# Dosing_CTRLR_HMI.net
KiCad netlist of a schematic drawn in EAGLE
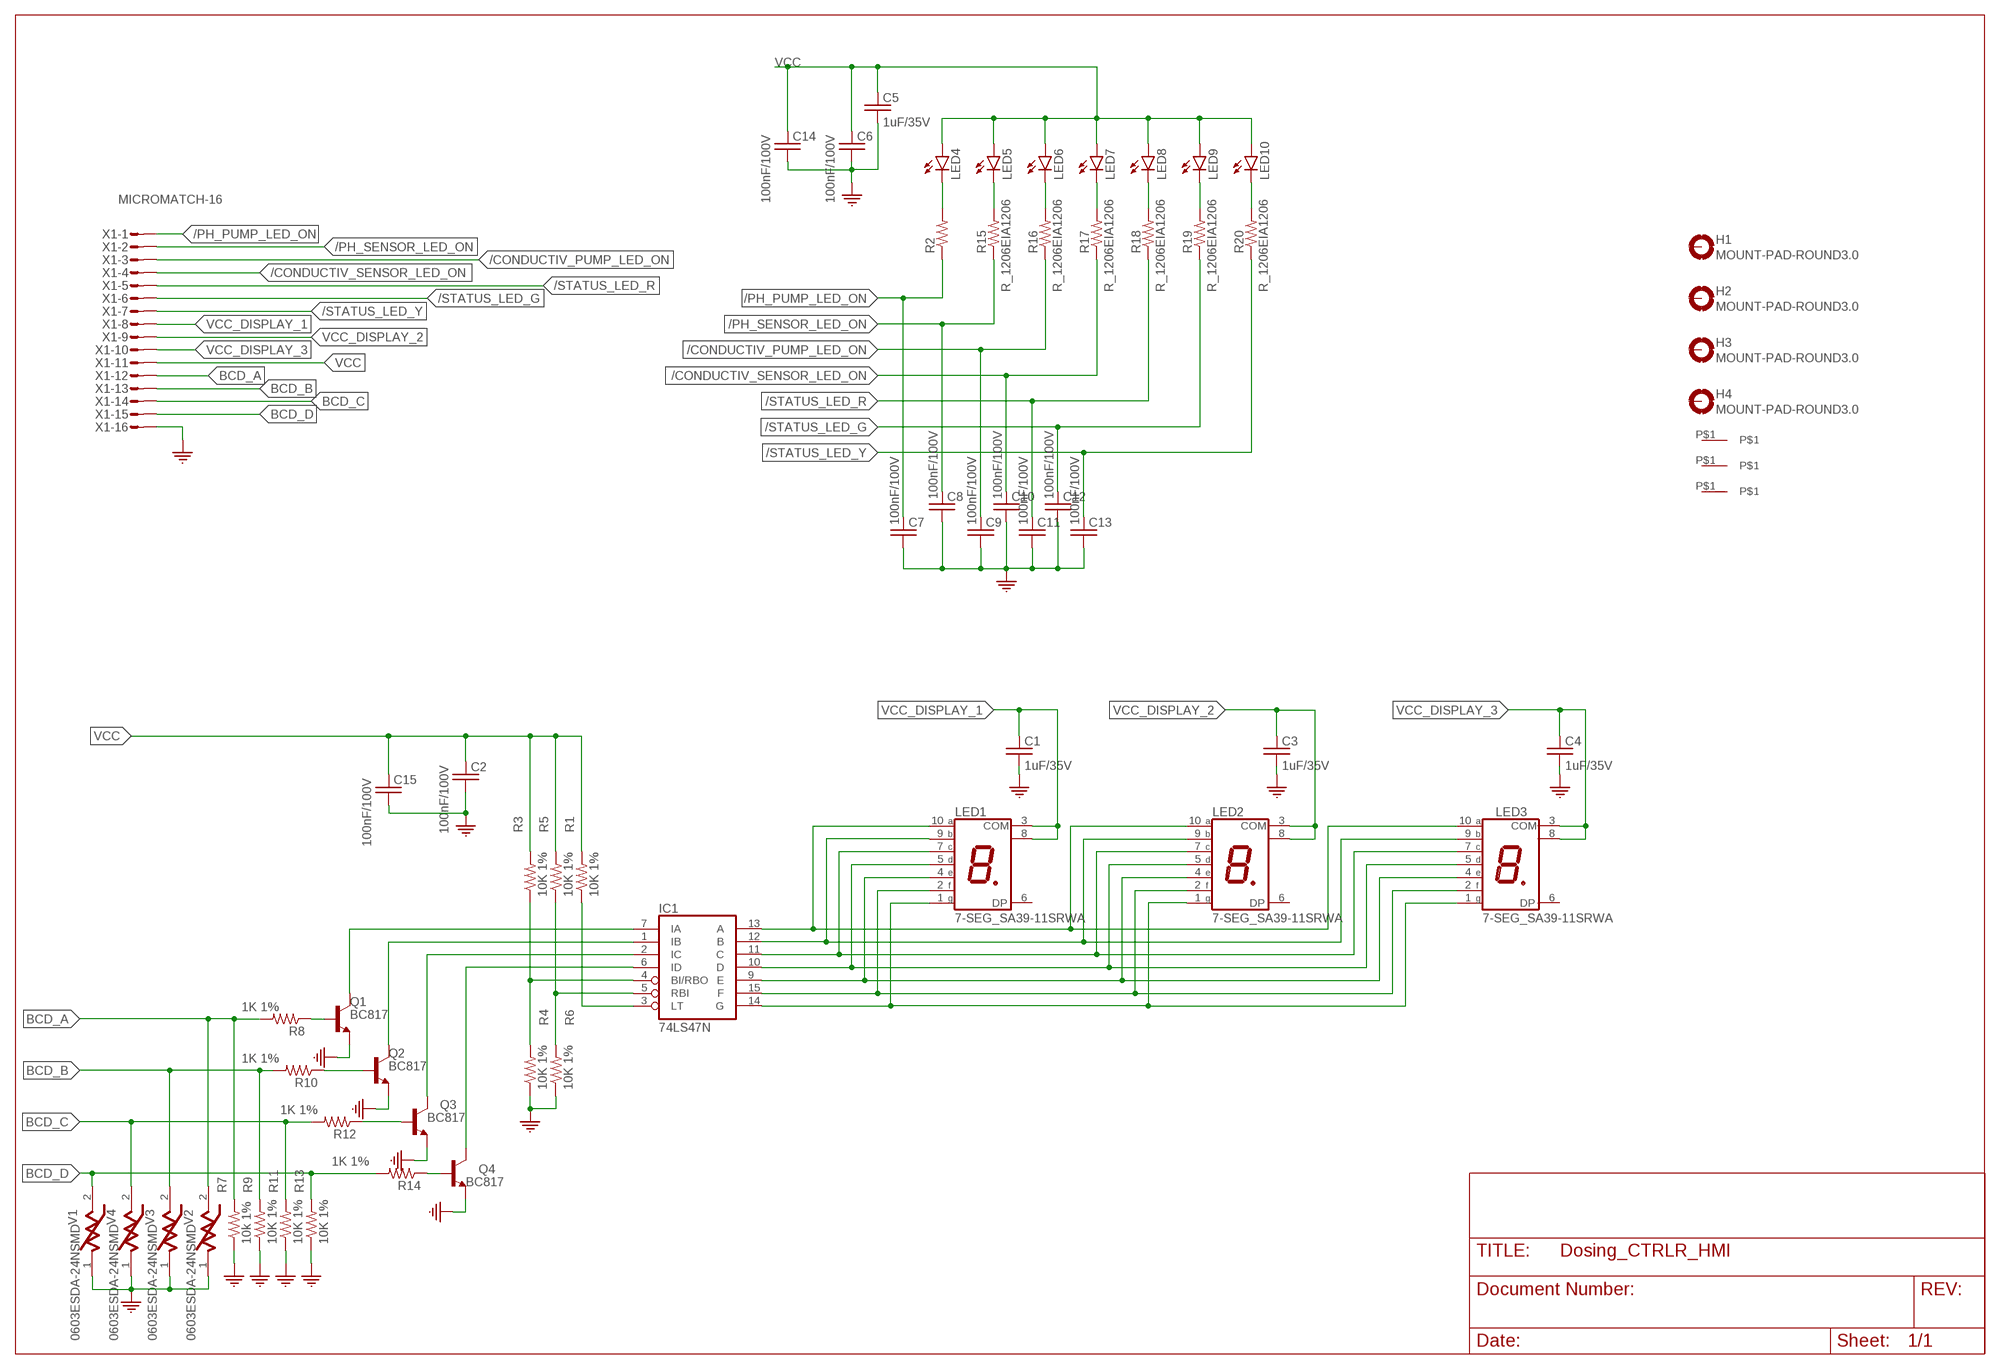
[diagram p0: schematic, sheet 1]

(export (version "E")
  (design (tool "Eeschema 10.0.6"))
  (components
    (comp (ref "C1")
      (value "1uF/35V")
      (footprint "eagle-import:EIA0603")
      (libsource (lib "eagle-import") (part "C_0603EIA0603"))
    )
    (comp (ref "C2")
      (value "100nF/100V")
      (footprint "eagle-import:EIA0603")
      (libsource (lib "eagle-import") (part "C_0603EIA0603"))
    )
    (comp (ref "C3")
      (value "1uF/35V")
      (footprint "eagle-import:EIA0603")
      (libsource (lib "eagle-import") (part "C_0603EIA0603"))
    )
    (comp (ref "C4")
      (value "1uF/35V")
      (footprint "eagle-import:EIA0603")
      (libsource (lib "eagle-import") (part "C_0603EIA0603"))
    )
    (comp (ref "C5")
      (value "1uF/35V")
      (footprint "eagle-import:EIA0603")
      (libsource (lib "eagle-import") (part "C_0603EIA0603"))
    )
    (comp (ref "C6")
      (value "100nF/100V")
      (footprint "eagle-import:EIA0603")
      (libsource (lib "eagle-import") (part "C_0603EIA0603"))
    )
    (comp (ref "C7")
      (value "100nF/100V")
      (footprint "eagle-import:EIA0603")
      (libsource (lib "eagle-import") (part "C_0603EIA0603"))
    )
    (comp (ref "C8")
      (value "100nF/100V")
      (footprint "eagle-import:EIA0603")
      (libsource (lib "eagle-import") (part "C_0603EIA0603"))
    )
    (comp (ref "C9")
      (value "100nF/100V")
      (footprint "eagle-import:EIA0603")
      (libsource (lib "eagle-import") (part "C_0603EIA0603"))
    )
    (comp (ref "C10")
      (value "100nF/100V")
      (footprint "eagle-import:EIA0603")
      (libsource (lib "eagle-import") (part "C_0603EIA0603"))
    )
    (comp (ref "C11")
      (value "100nF/100V")
      (footprint "eagle-import:EIA0603")
      (libsource (lib "eagle-import") (part "C_0603EIA0603"))
    )
    (comp (ref "C12")
      (value "100nF/100V")
      (footprint "eagle-import:EIA0603")
      (libsource (lib "eagle-import") (part "C_0603EIA0603"))
    )
    (comp (ref "C13")
      (value "100nF/100V")
      (footprint "eagle-import:EIA0603")
      (libsource (lib "eagle-import") (part "C_0603EIA0603"))
    )
    (comp (ref "C14")
      (value "100nF/100V")
      (footprint "eagle-import:EIA0603")
      (libsource (lib "eagle-import") (part "C_0603EIA0603"))
    )
    (comp (ref "C15")
      (value "100nF/100V")
      (footprint "eagle-import:EIA0603")
      (libsource (lib "eagle-import") (part "C_0603EIA0603"))
    )
    (comp (ref "FID1")
      (value "FIDUCIAL")
      (footprint "eagle-import:FIDUCIAL")
      (libsource (lib "eagle-import") (part "FIDUCIAL"))
    )
    (comp (ref "FID2")
      (value "FIDUCIAL")
      (footprint "eagle-import:FIDUCIAL")
      (libsource (lib "eagle-import") (part "FIDUCIAL"))
    )
    (comp (ref "FID3")
      (value "FIDUCIAL")
      (footprint "eagle-import:FIDUCIAL")
      (libsource (lib "eagle-import") (part "FIDUCIAL"))
    )
    (comp (ref "H1")
      (value "MOUNT-PAD-ROUND3.0")
      (footprint "eagle-import:3,0-PAD")
      (libsource (lib "eagle-import") (part "MOUNT-PAD-ROUND3.0"))
    )
    (comp (ref "H2")
      (value "MOUNT-PAD-ROUND3.0")
      (footprint "eagle-import:3,0-PAD")
      (libsource (lib "eagle-import") (part "MOUNT-PAD-ROUND3.0"))
    )
    (comp (ref "H3")
      (value "MOUNT-PAD-ROUND3.0")
      (footprint "eagle-import:3,0-PAD")
      (libsource (lib "eagle-import") (part "MOUNT-PAD-ROUND3.0"))
    )
    (comp (ref "H4")
      (value "MOUNT-PAD-ROUND3.0")
      (footprint "eagle-import:3,0-PAD")
      (libsource (lib "eagle-import") (part "MOUNT-PAD-ROUND3.0"))
    )
    (comp (ref "IC1")
      (value "74LS47N")
      (footprint "eagle-import:DIL16")
      (libsource (lib "eagle-import") (part "7447NLS"))
    )
    (comp (ref "LED1")
      (value "7-SEG_SA39-11SRWA")
      (footprint "eagle-import:SA39-11SRWA")
      (libsource (lib "eagle-import") (part "7-SEG_SA39-11SRWA"))
    )
    (comp (ref "LED2")
      (value "7-SEG_SA39-11SRWA")
      (footprint "eagle-import:SA39-11SRWA")
      (libsource (lib "eagle-import") (part "7-SEG_SA39-11SRWA"))
    )
    (comp (ref "LED3")
      (value "7-SEG_SA39-11SRWA")
      (footprint "eagle-import:SA39-11SRWA")
      (libsource (lib "eagle-import") (part "7-SEG_SA39-11SRWA"))
    )
    (comp (ref "LED4")
      (value "LED5MM")
      (footprint "eagle-import:LED5MM")
      (libsource (lib "eagle-import") (part "LED5MM"))
    )
    (comp (ref "LED5")
      (value "LED5MM")
      (footprint "eagle-import:LED5MM")
      (libsource (lib "eagle-import") (part "LED5MM"))
    )
    (comp (ref "LED6")
      (value "LED5MM")
      (footprint "eagle-import:LED5MM")
      (libsource (lib "eagle-import") (part "LED5MM"))
    )
    (comp (ref "LED7")
      (value "LED5MM")
      (footprint "eagle-import:LED5MM")
      (libsource (lib "eagle-import") (part "LED5MM"))
    )
    (comp (ref "LED8")
      (value "LED5MM")
      (footprint "eagle-import:LED5MM")
      (libsource (lib "eagle-import") (part "LED5MM"))
    )
    (comp (ref "LED9")
      (value "LED5MM")
      (footprint "eagle-import:LED5MM")
      (libsource (lib "eagle-import") (part "LED5MM"))
    )
    (comp (ref "LED10")
      (value "LED5MM")
      (footprint "eagle-import:LED5MM")
      (libsource (lib "eagle-import") (part "LED5MM"))
    )
    (comp (ref "Q1")
      (value "BC817")
      (footprint "eagle-import:SOT23")
      (fields (field (name "MFR") "NXP"))
      (libsource (lib "eagle-import") (part "BC817"))
    )
    (comp (ref "Q2")
      (value "BC817")
      (footprint "eagle-import:SOT23")
      (fields (field (name "MFR") "NXP"))
      (libsource (lib "eagle-import") (part "BC817"))
    )
    (comp (ref "Q3")
      (value "BC817")
      (footprint "eagle-import:SOT23")
      (fields (field (name "MFR") "NXP"))
      (libsource (lib "eagle-import") (part "BC817"))
    )
    (comp (ref "Q4")
      (value "BC817")
      (footprint "eagle-import:SOT23")
      (fields (field (name "MFR") "NXP"))
      (libsource (lib "eagle-import") (part "BC817"))
    )
    (comp (ref "R1")
      (value "10K 1%")
      (footprint "eagle-import:EIA0603")
      (libsource (lib "eagle-import") (part "R_0603"))
    )
    (comp (ref "R2")
      (value "R_1206EIA1206")
      (footprint "eagle-import:EIA1206")
      (libsource (lib "eagle-import") (part "R_1206EIA1206"))
    )
    (comp (ref "R3")
      (value "10K 1%")
      (footprint "eagle-import:EIA0603")
      (libsource (lib "eagle-import") (part "R_0603"))
    )
    (comp (ref "R4")
      (value "10K 1%")
      (footprint "eagle-import:EIA0603")
      (libsource (lib "eagle-import") (part "R_0603"))
    )
    (comp (ref "R5")
      (value "10K 1%")
      (footprint "eagle-import:EIA0603")
      (libsource (lib "eagle-import") (part "R_0603"))
    )
    (comp (ref "R6")
      (value "10K 1%")
      (footprint "eagle-import:EIA0603")
      (libsource (lib "eagle-import") (part "R_0603"))
    )
    (comp (ref "R7")
      (value "10k 1%")
      (footprint "eagle-import:EIA0603")
      (libsource (lib "eagle-import") (part "R_0603"))
    )
    (comp (ref "R8")
      (value "1K 1%")
      (footprint "eagle-import:EIA0603")
      (libsource (lib "eagle-import") (part "R_0603"))
    )
    (comp (ref "R9")
      (value "10K 1%")
      (footprint "eagle-import:EIA0603")
      (libsource (lib "eagle-import") (part "R_0603"))
    )
    (comp (ref "R10")
      (value "1K 1%")
      (footprint "eagle-import:EIA0603")
      (libsource (lib "eagle-import") (part "R_0603"))
    )
    (comp (ref "R11")
      (value "10K 1%")
      (footprint "eagle-import:EIA0603")
      (libsource (lib "eagle-import") (part "R_0603"))
    )
    (comp (ref "R12")
      (value "1K 1%")
      (footprint "eagle-import:EIA0603")
      (libsource (lib "eagle-import") (part "R_0603"))
    )
    (comp (ref "R13")
      (value "10K 1%")
      (footprint "eagle-import:EIA0603")
      (libsource (lib "eagle-import") (part "R_0603"))
    )
    (comp (ref "R14")
      (value "1K 1%")
      (footprint "eagle-import:EIA0603")
      (libsource (lib "eagle-import") (part "R_0603"))
    )
    (comp (ref "R15")
      (value "R_1206EIA1206")
      (footprint "eagle-import:EIA1206")
      (libsource (lib "eagle-import") (part "R_1206EIA1206"))
    )
    (comp (ref "R16")
      (value "R_1206EIA1206")
      (footprint "eagle-import:EIA1206")
      (libsource (lib "eagle-import") (part "R_1206EIA1206"))
    )
    (comp (ref "R17")
      (value "R_1206EIA1206")
      (footprint "eagle-import:EIA1206")
      (libsource (lib "eagle-import") (part "R_1206EIA1206"))
    )
    (comp (ref "R18")
      (value "R_1206EIA1206")
      (footprint "eagle-import:EIA1206")
      (libsource (lib "eagle-import") (part "R_1206EIA1206"))
    )
    (comp (ref "R19")
      (value "R_1206EIA1206")
      (footprint "eagle-import:EIA1206")
      (libsource (lib "eagle-import") (part "R_1206EIA1206"))
    )
    (comp (ref "R20")
      (value "R_1206EIA1206")
      (footprint "eagle-import:EIA1206")
      (libsource (lib "eagle-import") (part "R_1206EIA1206"))
    )
    (comp (ref "V1")
      (value "0603ESDA-24NSMD")
      (footprint "eagle-import:EIA0603")
      (fields (field (name "MFR") "Bourns"))
      (libsource (lib "eagle-import") (part "0603ESDA-24NSMD"))
    )
    (comp (ref "V2")
      (value "0603ESDA-24NSMD")
      (footprint "eagle-import:EIA0603")
      (fields (field (name "MFR") "Bourns"))
      (libsource (lib "eagle-import") (part "0603ESDA-24NSMD"))
    )
    (comp (ref "V3")
      (value "0603ESDA-24NSMD")
      (footprint "eagle-import:EIA0603")
      (fields (field (name "MFR") "Bourns"))
      (libsource (lib "eagle-import") (part "0603ESDA-24NSMD"))
    )
    (comp (ref "V4")
      (value "0603ESDA-24NSMD")
      (footprint "eagle-import:EIA0603")
      (fields (field (name "MFR") "Bourns"))
      (libsource (lib "eagle-import") (part "0603ESDA-24NSMD"))
    )
    (comp (ref "X1")
      (value "MICROMATCH-16")
      (footprint "eagle-import:MICROMATCH-16")
      (fields (field (name "MF") "FARNELL") (field (name "MPN") "8-215464-6"))
      (libsource (lib "eagle-import") (part "MICROMATCH-16"))
    )
  )
  (nets
    (net (code "1") (name "BCD_A") (class "Default")
      (node (ref "R7") (pin "2") (pinfunction "2_2") (pintype "passive"))
      (node (ref "R8") (pin "2") (pinfunction "2_2") (pintype "passive"))
      (node (ref "V2") (pin "2") (pinfunction "2_2") (pintype "passive"))
      (node (ref "X1") (pin "12") (pinfunction "S_12") (pintype "passive"))
    )
    (net (code "2") (name "BCD_B") (class "Default")
      (node (ref "R10") (pin "2") (pinfunction "2_2") (pintype "passive"))
      (node (ref "R9") (pin "2") (pinfunction "2_2") (pintype "passive"))
      (node (ref "V3") (pin "2") (pinfunction "2_2") (pintype "passive"))
      (node (ref "X1") (pin "13") (pinfunction "S_13") (pintype "passive"))
    )
    (net (code "3") (name "BCD_C") (class "Default")
      (node (ref "R11") (pin "2") (pinfunction "2_2") (pintype "passive"))
      (node (ref "R12") (pin "2") (pinfunction "2_2") (pintype "passive"))
      (node (ref "V4") (pin "2") (pinfunction "2_2") (pintype "passive"))
      (node (ref "X1") (pin "14") (pinfunction "S_14") (pintype "passive"))
    )
    (net (code "4") (name "BCD_D") (class "Default")
      (node (ref "R13") (pin "2") (pinfunction "2_2") (pintype "passive"))
      (node (ref "R14") (pin "2") (pinfunction "2_2") (pintype "passive"))
      (node (ref "V1") (pin "2") (pinfunction "2_2") (pintype "passive"))
      (node (ref "X1") (pin "15") (pinfunction "S_15") (pintype "passive"))
    )
    (net (code "5") (name "GND") (class "Default")
      (node (ref "C1") (pin "2") (pinfunction "2_2") (pintype "passive"))
      (node (ref "C10") (pin "2") (pinfunction "2_2") (pintype "passive"))
      (node (ref "C11") (pin "2") (pinfunction "2_2") (pintype "passive"))
      (node (ref "C12") (pin "2") (pinfunction "2_2") (pintype "passive"))
      (node (ref "C13") (pin "2") (pinfunction "2_2") (pintype "passive"))
      (node (ref "C14") (pin "2") (pinfunction "2_2") (pintype "passive"))
      (node (ref "C15") (pin "2") (pinfunction "2_2") (pintype "passive"))
      (node (ref "C2") (pin "2") (pinfunction "2_2") (pintype "passive"))
      (node (ref "C3") (pin "2") (pinfunction "2_2") (pintype "passive"))
      (node (ref "C4") (pin "2") (pinfunction "2_2") (pintype "passive"))
      (node (ref "C5") (pin "2") (pinfunction "2_2") (pintype "passive"))
      (node (ref "C6") (pin "2") (pinfunction "2_2") (pintype "passive"))
      (node (ref "C7") (pin "2") (pinfunction "2_2") (pintype "passive"))
      (node (ref "C8") (pin "2") (pinfunction "2_2") (pintype "passive"))
      (node (ref "C9") (pin "2") (pinfunction "2_2") (pintype "passive"))
      (node (ref "Q1") (pin "2") (pinfunction "E_2") (pintype "passive"))
      (node (ref "Q2") (pin "2") (pinfunction "E_2") (pintype "passive"))
      (node (ref "Q3") (pin "2") (pinfunction "E_2") (pintype "passive"))
      (node (ref "Q4") (pin "2") (pinfunction "E_2") (pintype "passive"))
      (node (ref "R11") (pin "1") (pinfunction "1_1") (pintype "passive"))
      (node (ref "R13") (pin "1") (pinfunction "1_1") (pintype "passive"))
      (node (ref "R4") (pin "1") (pinfunction "1_1") (pintype "passive"))
      (node (ref "R6") (pin "1") (pinfunction "1_1") (pintype "passive"))
      (node (ref "R7") (pin "1") (pinfunction "1_1") (pintype "passive"))
      (node (ref "R9") (pin "1") (pinfunction "1_1") (pintype "passive"))
      (node (ref "V1") (pin "1") (pinfunction "1_1") (pintype "passive"))
      (node (ref "V2") (pin "1") (pinfunction "1_1") (pintype "passive"))
      (node (ref "V3") (pin "1") (pinfunction "1_1") (pintype "passive"))
      (node (ref "V4") (pin "1") (pinfunction "1_1") (pintype "passive"))
      (node (ref "X1") (pin "16") (pinfunction "S_16") (pintype "passive"))
    )
    (net (code "6") (name "Net-(IC1A-A)") (class "Default")
      (node (ref "IC1") (pin "13") (pinfunction "A_13") (pintype "output"))
      (node (ref "LED1") (pin "10") (pinfunction "A_10") (pintype "passive"))
      (node (ref "LED2") (pin "10") (pinfunction "A_10") (pintype "passive"))
      (node (ref "LED3") (pin "10") (pinfunction "A_10") (pintype "passive"))
    )
    (net (code "7") (name "Net-(IC1A-B)") (class "Default")
      (node (ref "IC1") (pin "12") (pinfunction "B_12") (pintype "output"))
      (node (ref "LED1") (pin "9") (pinfunction "B_9") (pintype "passive"))
      (node (ref "LED2") (pin "9") (pinfunction "B_9") (pintype "passive"))
      (node (ref "LED3") (pin "9") (pinfunction "B_9") (pintype "passive"))
    )
    (net (code "8") (name "Net-(IC1A-BI{slash}RBO)") (class "Default")
      (node (ref "IC1") (pin "4") (pinfunction "BI/RBO_4") (pintype "input"))
      (node (ref "R3") (pin "1") (pinfunction "1_1") (pintype "passive"))
      (node (ref "R4") (pin "2") (pinfunction "2_2") (pintype "passive"))
    )
    (net (code "9") (name "Net-(IC1A-C)") (class "Default")
      (node (ref "IC1") (pin "11") (pinfunction "C_11") (pintype "output"))
      (node (ref "LED1") (pin "7") (pinfunction "C_7") (pintype "passive"))
      (node (ref "LED2") (pin "7") (pinfunction "C_7") (pintype "passive"))
      (node (ref "LED3") (pin "7") (pinfunction "C_7") (pintype "passive"))
    )
    (net (code "10") (name "Net-(IC1A-D)") (class "Default")
      (node (ref "IC1") (pin "10") (pinfunction "D_10") (pintype "output"))
      (node (ref "LED1") (pin "5") (pinfunction "D_5") (pintype "passive"))
      (node (ref "LED2") (pin "5") (pinfunction "D_5") (pintype "passive"))
      (node (ref "LED3") (pin "5") (pinfunction "D_5") (pintype "passive"))
    )
    (net (code "11") (name "Net-(IC1A-E)") (class "Default")
      (node (ref "IC1") (pin "9") (pinfunction "E_9") (pintype "output"))
      (node (ref "LED1") (pin "4") (pinfunction "E_4") (pintype "passive"))
      (node (ref "LED2") (pin "4") (pinfunction "E_4") (pintype "passive"))
      (node (ref "LED3") (pin "4") (pinfunction "E_4") (pintype "passive"))
    )
    (net (code "12") (name "Net-(IC1A-F)") (class "Default")
      (node (ref "IC1") (pin "15") (pinfunction "F_15") (pintype "output"))
      (node (ref "LED1") (pin "2") (pinfunction "F_2") (pintype "passive"))
      (node (ref "LED2") (pin "2") (pinfunction "F_2") (pintype "passive"))
      (node (ref "LED3") (pin "2") (pinfunction "F_2") (pintype "passive"))
    )
    (net (code "13") (name "Net-(IC1A-G)") (class "Default")
      (node (ref "IC1") (pin "14") (pinfunction "G_14") (pintype "output"))
      (node (ref "LED1") (pin "1") (pinfunction "G_1") (pintype "passive"))
      (node (ref "LED2") (pin "1") (pinfunction "G_1") (pintype "passive"))
      (node (ref "LED3") (pin "1") (pinfunction "G_1") (pintype "passive"))
    )
    (net (code "14") (name "Net-(IC1A-IA)") (class "Default")
      (node (ref "IC1") (pin "7") (pinfunction "IA_7") (pintype "input"))
      (node (ref "Q1") (pin "3") (pinfunction "C_3") (pintype "passive"))
    )
    (net (code "15") (name "Net-(IC1A-IB)") (class "Default")
      (node (ref "IC1") (pin "1") (pinfunction "IB_1") (pintype "input"))
      (node (ref "Q2") (pin "3") (pinfunction "C_3") (pintype "passive"))
    )
    (net (code "16") (name "Net-(IC1A-IC)") (class "Default")
      (node (ref "IC1") (pin "2") (pinfunction "IC_2") (pintype "input"))
      (node (ref "Q3") (pin "3") (pinfunction "C_3") (pintype "passive"))
    )
    (net (code "17") (name "Net-(IC1A-ID)") (class "Default")
      (node (ref "IC1") (pin "6") (pinfunction "ID_6") (pintype "input"))
      (node (ref "Q4") (pin "3") (pinfunction "C_3") (pintype "passive"))
    )
    (net (code "18") (name "Net-(IC1A-LT)") (class "Default")
      (node (ref "IC1") (pin "3") (pinfunction "LT_3") (pintype "input"))
      (node (ref "R1") (pin "1") (pinfunction "1_1") (pintype "passive"))
    )
    (net (code "19") (name "Net-(IC1A-RBI)") (class "Default")
      (node (ref "IC1") (pin "5") (pinfunction "RBI_5") (pintype "input"))
      (node (ref "R5") (pin "1") (pinfunction "1_1") (pintype "passive"))
      (node (ref "R6") (pin "2") (pinfunction "2_2") (pintype "passive"))
    )
    (net (code "20") (name "Net-(LED4-C)") (class "Default")
      (node (ref "LED4") (pin "K") (pinfunction "C_K") (pintype "passive"))
      (node (ref "R2") (pin "2") (pinfunction "2_2") (pintype "passive"))
    )
    (net (code "21") (name "Net-(LED5-C)") (class "Default")
      (node (ref "LED5") (pin "K") (pinfunction "C_K") (pintype "passive"))
      (node (ref "R15") (pin "2") (pinfunction "2_2") (pintype "passive"))
    )
    (net (code "22") (name "Net-(LED6-C)") (class "Default")
      (node (ref "LED6") (pin "K") (pinfunction "C_K") (pintype "passive"))
      (node (ref "R16") (pin "2") (pinfunction "2_2") (pintype "passive"))
    )
    (net (code "23") (name "Net-(LED7-C)") (class "Default")
      (node (ref "LED7") (pin "K") (pinfunction "C_K") (pintype "passive"))
      (node (ref "R17") (pin "2") (pinfunction "2_2") (pintype "passive"))
    )
    (net (code "24") (name "Net-(LED8-C)") (class "Default")
      (node (ref "LED8") (pin "K") (pinfunction "C_K") (pintype "passive"))
      (node (ref "R18") (pin "2") (pinfunction "2_2") (pintype "passive"))
    )
    (net (code "25") (name "Net-(LED9-C)") (class "Default")
      (node (ref "LED9") (pin "K") (pinfunction "C_K") (pintype "passive"))
      (node (ref "R19") (pin "2") (pinfunction "2_2") (pintype "passive"))
    )
    (net (code "26") (name "Net-(LED10-C)") (class "Default")
      (node (ref "LED10") (pin "K") (pinfunction "C_K") (pintype "passive"))
      (node (ref "R20") (pin "2") (pinfunction "2_2") (pintype "passive"))
    )
    (net (code "27") (name "Net-(Q1-B)") (class "Default")
      (node (ref "Q1") (pin "1") (pinfunction "B_1") (pintype "passive"))
      (node (ref "R8") (pin "1") (pinfunction "1_1") (pintype "passive"))
    )
    (net (code "28") (name "Net-(Q2-B)") (class "Default")
      (node (ref "Q2") (pin "1") (pinfunction "B_1") (pintype "passive"))
      (node (ref "R10") (pin "1") (pinfunction "1_1") (pintype "passive"))
    )
    (net (code "29") (name "Net-(Q3-B)") (class "Default")
      (node (ref "Q3") (pin "1") (pinfunction "B_1") (pintype "passive"))
      (node (ref "R12") (pin "1") (pinfunction "1_1") (pintype "passive"))
    )
    (net (code "30") (name "Net-(Q4-B)") (class "Default")
      (node (ref "Q4") (pin "1") (pinfunction "B_1") (pintype "passive"))
      (node (ref "R14") (pin "1") (pinfunction "1_1") (pintype "passive"))
    )
    (net (code "31") (name "VCC") (class "Default")
      (node (ref "C14") (pin "1") (pinfunction "1_1") (pintype "passive"))
      (node (ref "C15") (pin "1") (pinfunction "1_1") (pintype "passive"))
      (node (ref "C2") (pin "1") (pinfunction "1_1") (pintype "passive"))
      (node (ref "C5") (pin "1") (pinfunction "1_1") (pintype "passive"))
      (node (ref "C6") (pin "1") (pinfunction "1_1") (pintype "passive"))
      (node (ref "LED10") (pin "A") (pinfunction "A_A") (pintype "passive"))
      (node (ref "LED4") (pin "A") (pinfunction "A_A") (pintype "passive"))
      (node (ref "LED5") (pin "A") (pinfunction "A_A") (pintype "passive"))
      (node (ref "LED6") (pin "A") (pinfunction "A_A") (pintype "passive"))
      (node (ref "LED7") (pin "A") (pinfunction "A_A") (pintype "passive"))
      (node (ref "LED8") (pin "A") (pinfunction "A_A") (pintype "passive"))
      (node (ref "LED9") (pin "A") (pinfunction "A_A") (pintype "passive"))
      (node (ref "R1") (pin "2") (pinfunction "2_2") (pintype "passive"))
      (node (ref "R3") (pin "2") (pinfunction "2_2") (pintype "passive"))
      (node (ref "R5") (pin "2") (pinfunction "2_2") (pintype "passive"))
      (node (ref "X1") (pin "11") (pinfunction "S_11") (pintype "passive"))
    )
    (net (code "32") (name "VCC_DISPLAY_1") (class "Default")
      (node (ref "C1") (pin "1") (pinfunction "1_1") (pintype "passive"))
      (node (ref "LED1") (pin "3") (pinfunction "COM_3") (pintype "passive"))
      (node (ref "LED1") (pin "8") (pinfunction "COM_8") (pintype "passive"))
      (node (ref "X1") (pin "8") (pinfunction "S_8") (pintype "passive"))
    )
    (net (code "33") (name "VCC_DISPLAY_2") (class "Default")
      (node (ref "C3") (pin "1") (pinfunction "1_1") (pintype "passive"))
      (node (ref "LED2") (pin "3") (pinfunction "COM_3") (pintype "passive"))
      (node (ref "LED2") (pin "8") (pinfunction "COM_8") (pintype "passive"))
      (node (ref "X1") (pin "9") (pinfunction "S_9") (pintype "passive"))
    )
    (net (code "34") (name "VCC_DISPLAY_3") (class "Default")
      (node (ref "C4") (pin "1") (pinfunction "1_1") (pintype "passive"))
      (node (ref "LED3") (pin "3") (pinfunction "COM_3") (pintype "passive"))
      (node (ref "LED3") (pin "8") (pinfunction "COM_8") (pintype "passive"))
      (node (ref "X1") (pin "10") (pinfunction "S_10") (pintype "passive"))
    )
    (net (code "35") (name "unconnected-(FID1-PadP$1)") (class "Default")
      (node (ref "FID1") (pin "P$1") (pinfunction "P$1_P$1") (pintype "bidirectional"))
    )
    (net (code "36") (name "unconnected-(FID2-PadP$1)") (class "Default")
      (node (ref "FID2") (pin "P$1") (pinfunction "P$1_P$1") (pintype "bidirectional"))
    )
    (net (code "37") (name "unconnected-(FID3-PadP$1)") (class "Default")
      (node (ref "FID3") (pin "P$1") (pinfunction "P$1_P$1") (pintype "bidirectional"))
    )
    (net (code "38") (name "unconnected-(H1-MOUNT-PadB3,0)") (class "Default")
      (node (ref "H1") (pin "B3,0") (pinfunction "MOUNT_B3,0") (pintype "passive"))
    )
    (net (code "39") (name "unconnected-(H2-MOUNT-PadB3,0)") (class "Default")
      (node (ref "H2") (pin "B3,0") (pinfunction "MOUNT_B3,0") (pintype "passive"))
    )
    (net (code "40") (name "unconnected-(H3-MOUNT-PadB3,0)") (class "Default")
      (node (ref "H3") (pin "B3,0") (pinfunction "MOUNT_B3,0") (pintype "passive"))
    )
    (net (code "41") (name "unconnected-(H4-MOUNT-PadB3,0)") (class "Default")
      (node (ref "H4") (pin "B3,0") (pinfunction "MOUNT_B3,0") (pintype "passive"))
    )
    (net (code "42") (name "unconnected-(LED1-DP-Pad6)") (class "Default")
      (node (ref "LED1") (pin "6") (pinfunction "DP_6") (pintype "passive"))
    )
    (net (code "43") (name "unconnected-(LED2-DP-Pad6)") (class "Default")
      (node (ref "LED2") (pin "6") (pinfunction "DP_6") (pintype "passive"))
    )
    (net (code "44") (name "unconnected-(LED3-DP-Pad6)") (class "Default")
      (node (ref "LED3") (pin "6") (pinfunction "DP_6") (pintype "passive"))
    )
    (net (code "45") (name "{slash}CONDUCTIV_PUMP_LED_ON") (class "Default")
      (node (ref "C9") (pin "1") (pinfunction "1_1") (pintype "passive"))
      (node (ref "R16") (pin "1") (pinfunction "1_1") (pintype "passive"))
      (node (ref "X1") (pin "3") (pinfunction "S_3") (pintype "passive"))
    )
    (net (code "46") (name "{slash}CONDUCTIV_SENSOR_LED_ON") (class "Default")
      (node (ref "C10") (pin "1") (pinfunction "1_1") (pintype "passive"))
      (node (ref "R17") (pin "1") (pinfunction "1_1") (pintype "passive"))
      (node (ref "X1") (pin "4") (pinfunction "S_4") (pintype "passive"))
    )
    (net (code "47") (name "{slash}PH_PUMP_LED_ON") (class "Default")
      (node (ref "C7") (pin "1") (pinfunction "1_1") (pintype "passive"))
      (node (ref "R2") (pin "1") (pinfunction "1_1") (pintype "passive"))
      (node (ref "X1") (pin "1") (pinfunction "S_1") (pintype "passive"))
    )
    (net (code "48") (name "{slash}PH_SENSOR_LED_ON") (class "Default")
      (node (ref "C8") (pin "1") (pinfunction "1_1") (pintype "passive"))
      (node (ref "R15") (pin "1") (pinfunction "1_1") (pintype "passive"))
      (node (ref "X1") (pin "2") (pinfunction "S_2") (pintype "passive"))
    )
    (net (code "49") (name "{slash}STATUS_LED_G") (class "Default")
      (node (ref "C12") (pin "1") (pinfunction "1_1") (pintype "passive"))
      (node (ref "R19") (pin "1") (pinfunction "1_1") (pintype "passive"))
      (node (ref "X1") (pin "6") (pinfunction "S_6") (pintype "passive"))
    )
    (net (code "50") (name "{slash}STATUS_LED_R") (class "Default")
      (node (ref "C11") (pin "1") (pinfunction "1_1") (pintype "passive"))
      (node (ref "R18") (pin "1") (pinfunction "1_1") (pintype "passive"))
      (node (ref "X1") (pin "5") (pinfunction "S_5") (pintype "passive"))
    )
    (net (code "51") (name "{slash}STATUS_LED_Y") (class "Default")
      (node (ref "C13") (pin "1") (pinfunction "1_1") (pintype "passive"))
      (node (ref "R20") (pin "1") (pinfunction "1_1") (pintype "passive"))
      (node (ref "X1") (pin "7") (pinfunction "S_7") (pintype "passive"))
    )
  )
)
